# CoCoMEM_RAM.net
KiCad netlist of a schematic drawn in EAGLE
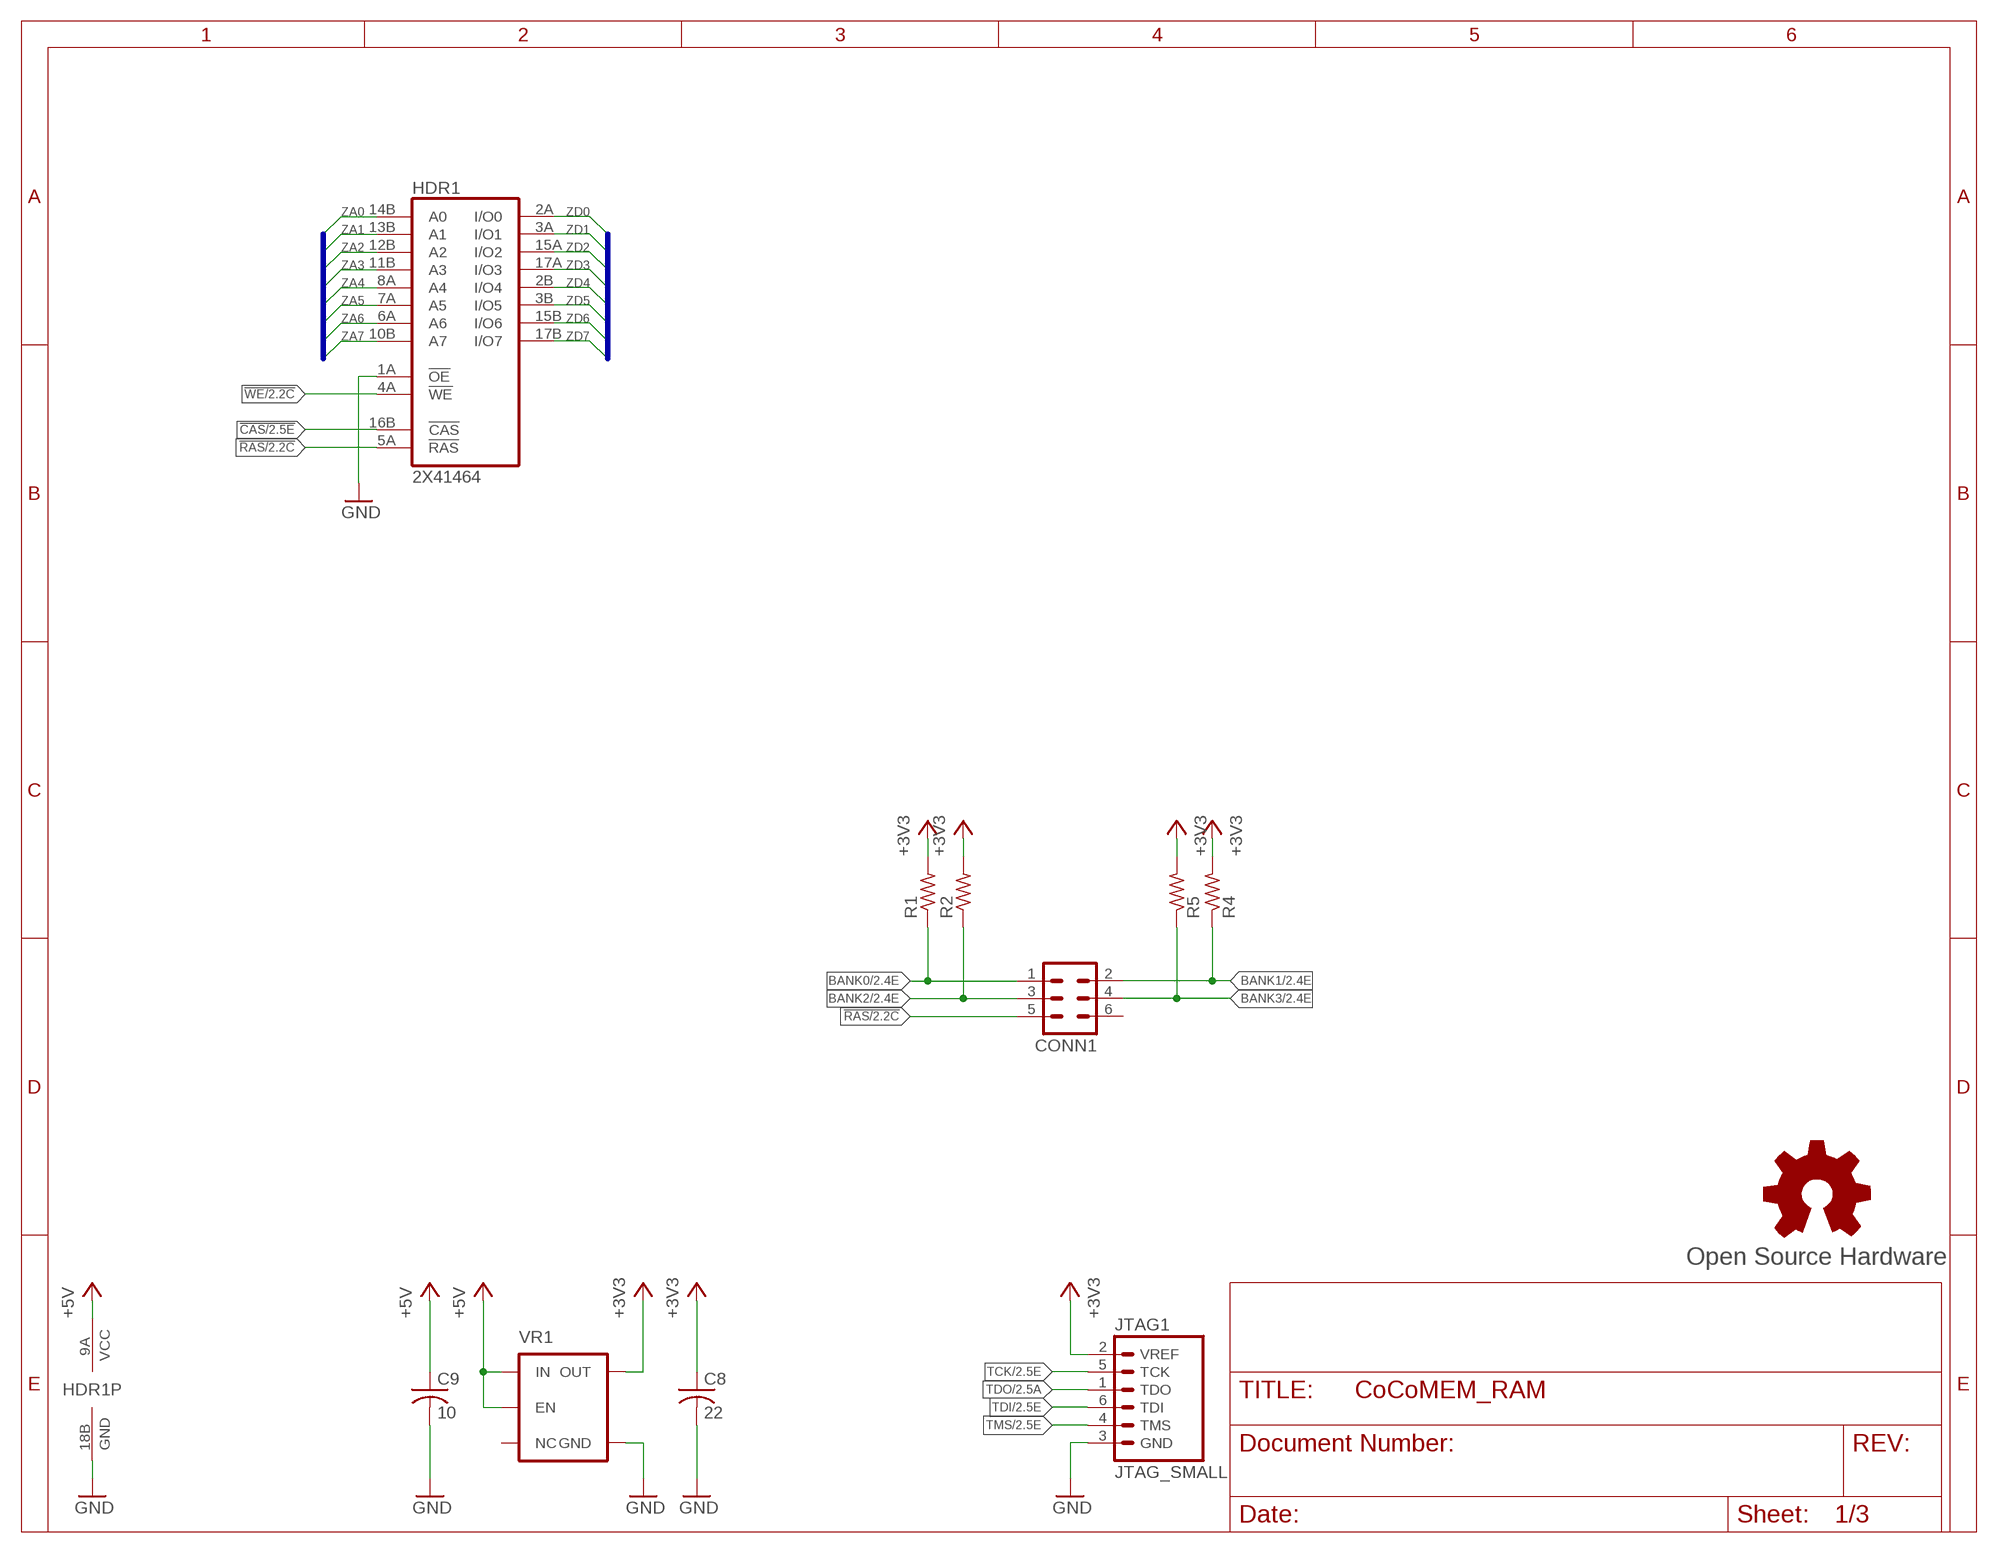
[diagram p0: schematic, sheet 1]
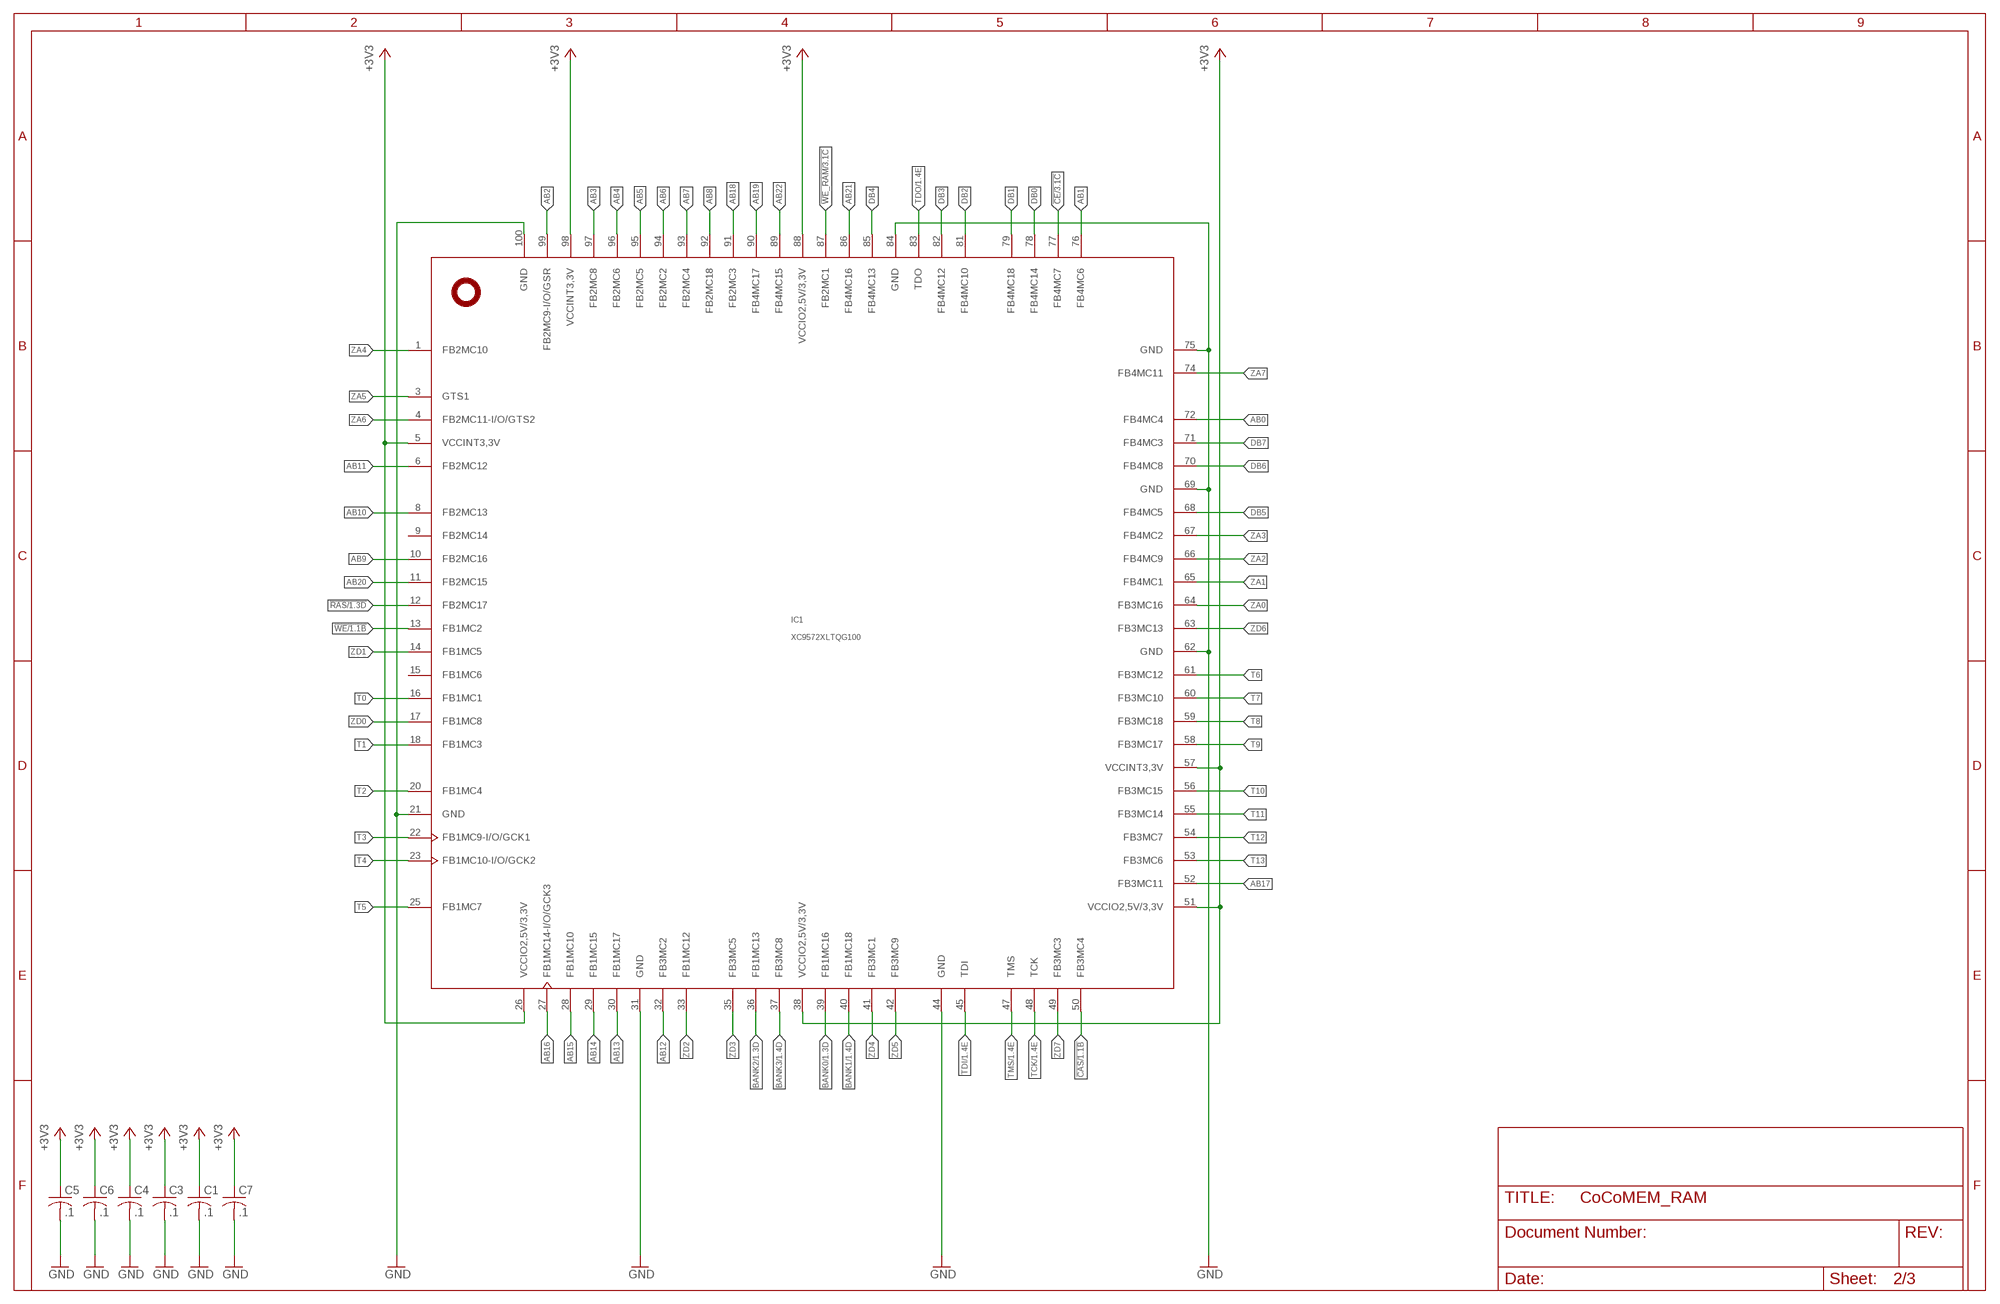
[diagram p1: schematic, sheet 2]
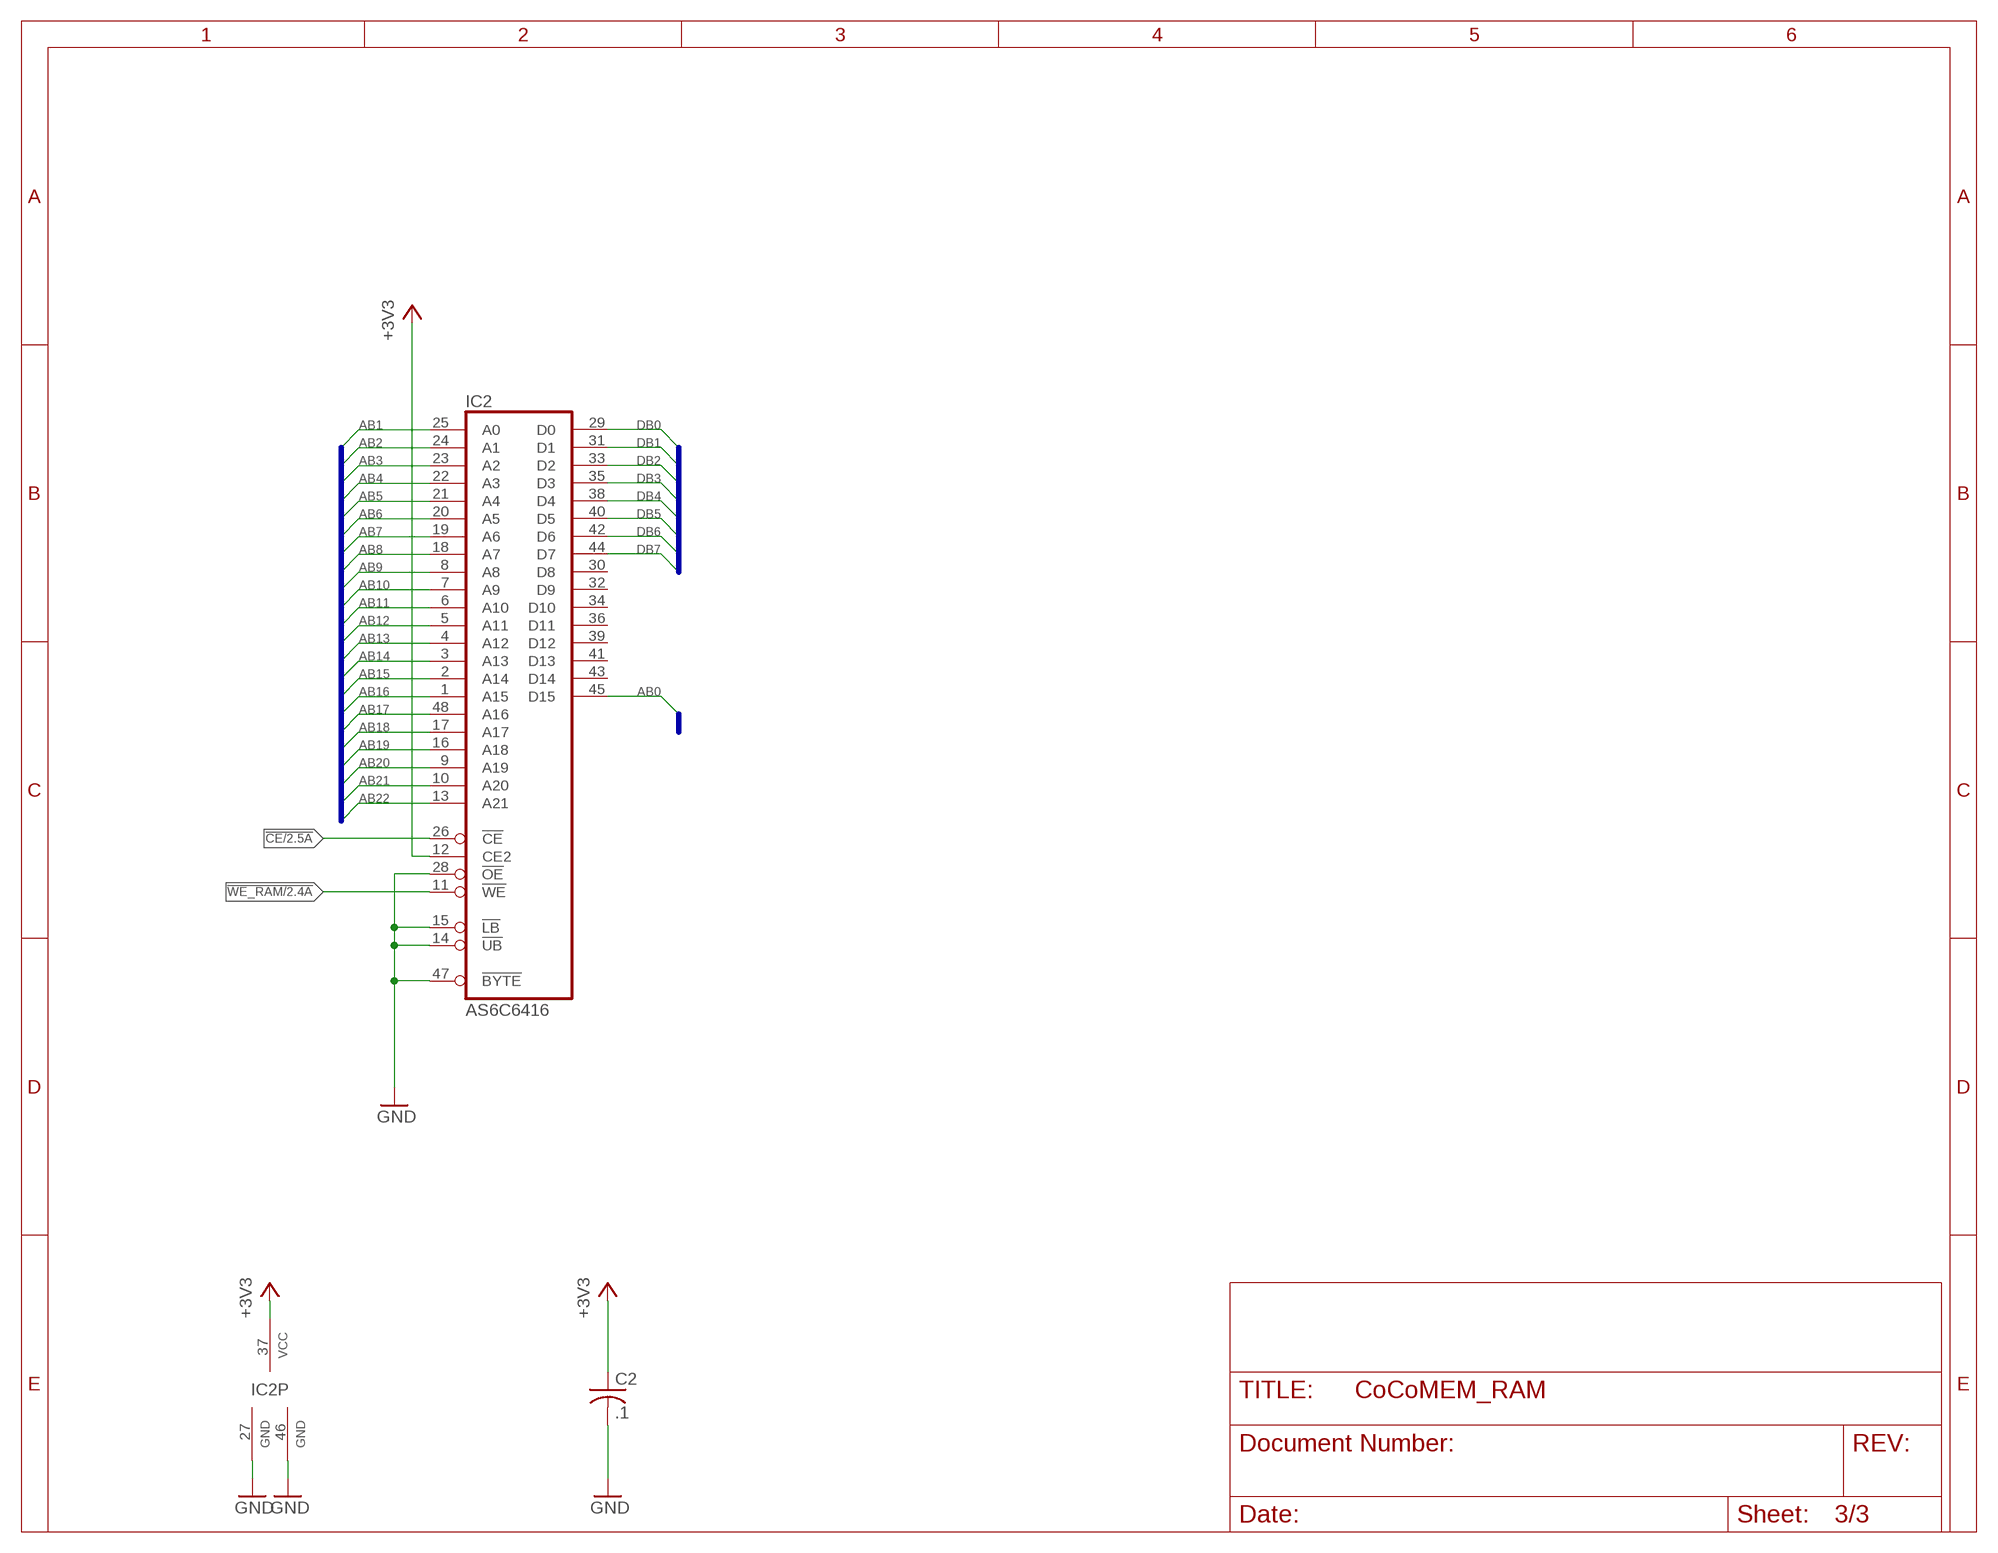
[diagram p2: schematic, sheet 3]

(export (version "E")
  (design (tool "Eeschema 10.0.6"))
  (components
    (comp (ref "C2")
      (value ".1")
      (footprint "eagle-import:C0603")
      (libsource (lib "eagle-import") (part "C-USC0603"))
    )
    (comp (ref "IC2")
      (value "AS6C6416")
      (footprint "eagle-import:TSOP48")
      (libsource (lib "eagle-import") (part "AS6C6416"))
    )
    (comp (ref "C1")
      (value ".1")
      (footprint "eagle-import:C0603")
      (libsource (lib "eagle-import") (part "C-USC0603"))
    )
    (comp (ref "C3")
      (value ".1")
      (footprint "eagle-import:C0603")
      (libsource (lib "eagle-import") (part "C-USC0603"))
    )
    (comp (ref "C4")
      (value ".1")
      (footprint "eagle-import:C0603")
      (libsource (lib "eagle-import") (part "C-USC0603"))
    )
    (comp (ref "C5")
      (value ".1")
      (footprint "eagle-import:C0603")
      (libsource (lib "eagle-import") (part "C-USC0603"))
    )
    (comp (ref "C6")
      (value ".1")
      (footprint "eagle-import:C0603")
      (libsource (lib "eagle-import") (part "C-USC0603"))
    )
    (comp (ref "C7")
      (value ".1")
      (footprint "eagle-import:C0603")
      (libsource (lib "eagle-import") (part "C-USC0603"))
    )
    (comp (ref "IC1")
      (value "XC9572XLTQG100")
      (footprint "eagle-import:TQFP100")
      (libsource (lib "eagle-import") (part "XC9572XLTQG100"))
    )
    (comp (ref "C8")
      (value "22")
      (footprint "eagle-import:C0805")
      (libsource (lib "eagle-import") (part "resistor_C-USC0805"))
    )
    (comp (ref "C9")
      (value "10")
      (footprint "eagle-import:C0805")
      (libsource (lib "eagle-import") (part "resistor_C-USC0805"))
    )
    (comp (ref "CONN1")
      (value "MA03-2")
      (footprint "eagle-import:MA03-2")
      (libsource (lib "eagle-import") (part "MA03-2"))
    )
    (comp (ref "GOLD_ORB_SM1")
      (value "Open Source Hardware")
      (footprint "eagle-import:OSHW_5MM")
      (libsource (lib "eagle-import") (part "OSHWLOGOLOGO5MM"))
    )
    (comp (ref "HDR1")
      (value "2X41464")
      (footprint "eagle-import:2XDIL18_REV")
      (libsource (lib "eagle-import") (part "2X41464"))
    )
    (comp (ref "JTAG1")
      (value "JTAG_SMALL")
      (footprint "eagle-import:JTAG-6")
      (libsource (lib "eagle-import") (part "JTAG_SMALL"))
    )
    (comp (ref "R1")
      (value "R-US_R0402")
      (footprint "eagle-import:R0402")
      (libsource (lib "eagle-import") (part "R-US_R0402"))
    )
    (comp (ref "R2")
      (value "R-US_R0402")
      (footprint "eagle-import:R0402")
      (libsource (lib "eagle-import") (part "R-US_R0402"))
    )
    (comp (ref "R4")
      (value "R-US_R0402")
      (footprint "eagle-import:R0402")
      (libsource (lib "eagle-import") (part "R-US_R0402"))
    )
    (comp (ref "R5")
      (value "R-US_R0402")
      (footprint "eagle-import:R0402")
      (libsource (lib "eagle-import") (part "R-US_R0402"))
    )
    (comp (ref "VR1")
      (value "V_REG_TPS76433SOT23-5")
      (footprint "eagle-import:SOT23-5")
      (libsource (lib "eagle-import") (part "V_REG_TPS76433SOT23-5"))
    )
  )
  (nets
    (net (code "1") (name "+3V3") (class "Default")
      (node (ref "C1") (pin "1") (pinfunction "1_1") (pintype "passive"))
      (node (ref "C2") (pin "1") (pinfunction "1_1") (pintype "passive"))
      (node (ref "C3") (pin "1") (pinfunction "1_1") (pintype "passive"))
      (node (ref "C4") (pin "1") (pinfunction "1_1") (pintype "passive"))
      (node (ref "C5") (pin "1") (pinfunction "1_1") (pintype "passive"))
      (node (ref "C6") (pin "1") (pinfunction "1_1") (pintype "passive"))
      (node (ref "C7") (pin "1") (pinfunction "1_1") (pintype "passive"))
      (node (ref "C8") (pin "1") (pinfunction "1_1") (pintype "passive"))
      (node (ref "IC1") (pin "26") (pinfunction "VCCIO2,5V/3,3V_26") (pintype "power_in"))
      (node (ref "IC1") (pin "38") (pinfunction "VCCIO2,5V/3,3V_38") (pintype "power_in"))
      (node (ref "IC1") (pin "5") (pinfunction "VCCINT3,3V_5") (pintype "power_in"))
      (node (ref "IC1") (pin "51") (pinfunction "VCCIO2,5V/3,3V_51") (pintype "power_in"))
      (node (ref "IC1") (pin "57") (pinfunction "VCCINT3,3V_57") (pintype "power_in"))
      (node (ref "IC1") (pin "88") (pinfunction "VCCIO2,5V/3,3V_88") (pintype "power_in"))
      (node (ref "IC1") (pin "98") (pinfunction "VCCINT3,3V_98") (pintype "power_in"))
      (node (ref "IC2") (pin "12") (pinfunction "CE2_12") (pintype "input"))
      (node (ref "IC2") (pin "37") (pinfunction "VCC_37") (pintype "power_in"))
      (node (ref "JTAG1") (pin "2") (pinfunction "VREF_2") (pintype "power_in"))
      (node (ref "R1") (pin "2") (pinfunction "2_2") (pintype "passive"))
      (node (ref "R2") (pin "2") (pinfunction "2_2") (pintype "passive"))
      (node (ref "R4") (pin "2") (pinfunction "2_2") (pintype "passive"))
      (node (ref "R5") (pin "2") (pinfunction "2_2") (pintype "passive"))
      (node (ref "VR1") (pin "5") (pinfunction "OUT_5") (pintype "passive"))
    )
    (net (code "2") (name "+5V") (class "Default")
      (node (ref "C9") (pin "1") (pinfunction "1_1") (pintype "passive"))
      (node (ref "HDR1") (pin "9A") (pinfunction "VCC_9A") (pintype "power_in"))
      (node (ref "VR1") (pin "1") (pinfunction "IN_1") (pintype "input"))
      (node (ref "VR1") (pin "3") (pinfunction "EN_3") (pintype "input"))
    )
    (net (code "3") (name "AB0") (class "Default")
      (node (ref "IC1") (pin "72") (pinfunction "FB4MC4_72") (pintype "bidirectional"))
      (node (ref "IC2") (pin "45") (pinfunction "D15_45") (pintype "bidirectional"))
    )
    (net (code "4") (name "AB1") (class "Default")
      (node (ref "IC1") (pin "76") (pinfunction "FB4MC6_76") (pintype "bidirectional"))
      (node (ref "IC2") (pin "25") (pinfunction "A0_25") (pintype "input"))
    )
    (net (code "5") (name "AB2") (class "Default")
      (node (ref "IC1") (pin "99") (pinfunction "FB2MC9-I/O/GSR_99") (pintype "bidirectional"))
      (node (ref "IC2") (pin "24") (pinfunction "A1_24") (pintype "input"))
    )
    (net (code "6") (name "AB3") (class "Default")
      (node (ref "IC1") (pin "97") (pinfunction "FB2MC8_97") (pintype "bidirectional"))
      (node (ref "IC2") (pin "23") (pinfunction "A2_23") (pintype "input"))
    )
    (net (code "7") (name "AB4") (class "Default")
      (node (ref "IC1") (pin "96") (pinfunction "FB2MC6_96") (pintype "bidirectional"))
      (node (ref "IC2") (pin "22") (pinfunction "A3_22") (pintype "input"))
    )
    (net (code "8") (name "AB5") (class "Default")
      (node (ref "IC1") (pin "95") (pinfunction "FB2MC5_95") (pintype "bidirectional"))
      (node (ref "IC2") (pin "21") (pinfunction "A4_21") (pintype "input"))
    )
    (net (code "9") (name "AB6") (class "Default")
      (node (ref "IC1") (pin "94") (pinfunction "FB2MC2_94") (pintype "bidirectional"))
      (node (ref "IC2") (pin "20") (pinfunction "A5_20") (pintype "input"))
    )
    (net (code "10") (name "AB7") (class "Default")
      (node (ref "IC1") (pin "93") (pinfunction "FB2MC4_93") (pintype "bidirectional"))
      (node (ref "IC2") (pin "19") (pinfunction "A6_19") (pintype "input"))
    )
    (net (code "11") (name "AB8") (class "Default")
      (node (ref "IC1") (pin "92") (pinfunction "FB2MC18_92") (pintype "bidirectional"))
      (node (ref "IC2") (pin "18") (pinfunction "A7_18") (pintype "input"))
    )
    (net (code "12") (name "AB9") (class "Default")
      (node (ref "IC1") (pin "10") (pinfunction "FB2MC16_10") (pintype "bidirectional"))
      (node (ref "IC2") (pin "8") (pinfunction "A8_8") (pintype "input"))
    )
    (net (code "13") (name "AB10") (class "Default")
      (node (ref "IC1") (pin "8") (pinfunction "FB2MC13_8") (pintype "bidirectional"))
      (node (ref "IC2") (pin "7") (pinfunction "A9_7") (pintype "input"))
    )
    (net (code "14") (name "AB11") (class "Default")
      (node (ref "IC1") (pin "6") (pinfunction "FB2MC12_6") (pintype "bidirectional"))
      (node (ref "IC2") (pin "6") (pinfunction "A10_6") (pintype "input"))
    )
    (net (code "15") (name "AB12") (class "Default")
      (node (ref "IC1") (pin "32") (pinfunction "FB3MC2_32") (pintype "bidirectional"))
      (node (ref "IC2") (pin "5") (pinfunction "A11_5") (pintype "input"))
    )
    (net (code "16") (name "AB13") (class "Default")
      (node (ref "IC1") (pin "30") (pinfunction "FB1MC17_30") (pintype "bidirectional"))
      (node (ref "IC2") (pin "4") (pinfunction "A12_4") (pintype "input"))
    )
    (net (code "17") (name "AB14") (class "Default")
      (node (ref "IC1") (pin "29") (pinfunction "FB1MC15_29") (pintype "bidirectional"))
      (node (ref "IC2") (pin "3") (pinfunction "A13_3") (pintype "input"))
    )
    (net (code "18") (name "AB15") (class "Default")
      (node (ref "IC1") (pin "28") (pinfunction "FB1MC10_28") (pintype "bidirectional"))
      (node (ref "IC2") (pin "2") (pinfunction "A14_2") (pintype "input"))
    )
    (net (code "19") (name "AB16") (class "Default")
      (node (ref "IC1") (pin "27") (pinfunction "FB1MC14-I/O/GCK3_27") (pintype "bidirectional"))
      (node (ref "IC2") (pin "1") (pinfunction "A15_1") (pintype "input"))
    )
    (net (code "20") (name "AB17") (class "Default")
      (node (ref "IC1") (pin "52") (pinfunction "FB3MC11_52") (pintype "bidirectional"))
      (node (ref "IC2") (pin "48") (pinfunction "A16_48") (pintype "input"))
    )
    (net (code "21") (name "AB18") (class "Default")
      (node (ref "IC1") (pin "91") (pinfunction "FB2MC3_91") (pintype "bidirectional"))
      (node (ref "IC2") (pin "17") (pinfunction "A17_17") (pintype "input"))
    )
    (net (code "22") (name "AB19") (class "Default")
      (node (ref "IC1") (pin "90") (pinfunction "FB4MC17_90") (pintype "bidirectional"))
      (node (ref "IC2") (pin "16") (pinfunction "A18_16") (pintype "input"))
    )
    (net (code "23") (name "AB20") (class "Default")
      (node (ref "IC1") (pin "11") (pinfunction "FB2MC15_11") (pintype "bidirectional"))
      (node (ref "IC2") (pin "9") (pinfunction "A19_9") (pintype "input"))
    )
    (net (code "24") (name "AB21") (class "Default")
      (node (ref "IC1") (pin "86") (pinfunction "FB4MC16_86") (pintype "bidirectional"))
      (node (ref "IC2") (pin "10") (pinfunction "A20_10") (pintype "input"))
    )
    (net (code "25") (name "AB22") (class "Default")
      (node (ref "IC1") (pin "89") (pinfunction "FB4MC15_89") (pintype "bidirectional"))
      (node (ref "IC2") (pin "13") (pinfunction "A21_13") (pintype "input"))
    )
    (net (code "26") (name "BANK0") (class "Default")
      (node (ref "CONN1") (pin "1") (pinfunction "1_1") (pintype "passive"))
      (node (ref "IC1") (pin "39") (pinfunction "FB1MC16_39") (pintype "bidirectional"))
      (node (ref "R1") (pin "1") (pinfunction "1_1") (pintype "passive"))
    )
    (net (code "27") (name "BANK1") (class "Default")
      (node (ref "CONN1") (pin "2") (pinfunction "2_2") (pintype "passive"))
      (node (ref "IC1") (pin "40") (pinfunction "FB1MC18_40") (pintype "bidirectional"))
      (node (ref "R4") (pin "1") (pinfunction "1_1") (pintype "passive"))
    )
    (net (code "28") (name "BANK2") (class "Default")
      (node (ref "CONN1") (pin "3") (pinfunction "3_3") (pintype "passive"))
      (node (ref "IC1") (pin "36") (pinfunction "FB1MC13_36") (pintype "bidirectional"))
      (node (ref "R2") (pin "1") (pinfunction "1_1") (pintype "passive"))
    )
    (net (code "29") (name "BANK3") (class "Default")
      (node (ref "CONN1") (pin "4") (pinfunction "4_4") (pintype "passive"))
      (node (ref "IC1") (pin "37") (pinfunction "FB3MC8_37") (pintype "bidirectional"))
      (node (ref "R5") (pin "1") (pinfunction "1_1") (pintype "passive"))
    )
    (net (code "30") (name "DB0") (class "Default")
      (node (ref "IC1") (pin "78") (pinfunction "FB4MC14_78") (pintype "bidirectional"))
      (node (ref "IC2") (pin "29") (pinfunction "D0_29") (pintype "bidirectional"))
    )
    (net (code "31") (name "DB1") (class "Default")
      (node (ref "IC1") (pin "79") (pinfunction "FB4MC18_79") (pintype "bidirectional"))
      (node (ref "IC2") (pin "31") (pinfunction "D1_31") (pintype "bidirectional"))
    )
    (net (code "32") (name "DB2") (class "Default")
      (node (ref "IC1") (pin "81") (pinfunction "FB4MC10_81") (pintype "bidirectional"))
      (node (ref "IC2") (pin "33") (pinfunction "D2_33") (pintype "bidirectional"))
    )
    (net (code "33") (name "DB3") (class "Default")
      (node (ref "IC1") (pin "82") (pinfunction "FB4MC12_82") (pintype "bidirectional"))
      (node (ref "IC2") (pin "35") (pinfunction "D3_35") (pintype "bidirectional"))
    )
    (net (code "34") (name "DB4") (class "Default")
      (node (ref "IC1") (pin "85") (pinfunction "FB4MC13_85") (pintype "bidirectional"))
      (node (ref "IC2") (pin "38") (pinfunction "D4_38") (pintype "bidirectional"))
    )
    (net (code "35") (name "DB5") (class "Default")
      (node (ref "IC1") (pin "68") (pinfunction "FB4MC5_68") (pintype "bidirectional"))
      (node (ref "IC2") (pin "40") (pinfunction "D5_40") (pintype "bidirectional"))
    )
    (net (code "36") (name "DB6") (class "Default")
      (node (ref "IC1") (pin "70") (pinfunction "FB4MC8_70") (pintype "bidirectional"))
      (node (ref "IC2") (pin "42") (pinfunction "D6_42") (pintype "bidirectional"))
    )
    (net (code "37") (name "DB7") (class "Default")
      (node (ref "IC1") (pin "71") (pinfunction "FB4MC3_71") (pintype "bidirectional"))
      (node (ref "IC2") (pin "44") (pinfunction "D7_44") (pintype "bidirectional"))
    )
    (net (code "38") (name "GND") (class "Default")
      (node (ref "C1") (pin "2") (pinfunction "2_2") (pintype "passive"))
      (node (ref "C2") (pin "2") (pinfunction "2_2") (pintype "passive"))
      (node (ref "C3") (pin "2") (pinfunction "2_2") (pintype "passive"))
      (node (ref "C4") (pin "2") (pinfunction "2_2") (pintype "passive"))
      (node (ref "C5") (pin "2") (pinfunction "2_2") (pintype "passive"))
      (node (ref "C6") (pin "2") (pinfunction "2_2") (pintype "passive"))
      (node (ref "C7") (pin "2") (pinfunction "2_2") (pintype "passive"))
      (node (ref "C8") (pin "2") (pinfunction "2_2") (pintype "passive"))
      (node (ref "C9") (pin "2") (pinfunction "2_2") (pintype "passive"))
      (node (ref "HDR1") (pin "18B") (pinfunction "GND_18B") (pintype "power_in"))
      (node (ref "HDR1") (pin "1A") (pinfunction "~{OE}_1A") (pintype "input"))
      (node (ref "IC1") (pin "100") (pinfunction "GND_100") (pintype "power_in"))
      (node (ref "IC1") (pin "21") (pinfunction "GND_21") (pintype "power_in"))
      (node (ref "IC1") (pin "31") (pinfunction "GND_31") (pintype "power_in"))
      (node (ref "IC1") (pin "44") (pinfunction "GND_44") (pintype "power_in"))
      (node (ref "IC1") (pin "62") (pinfunction "GND_62") (pintype "power_in"))
      (node (ref "IC1") (pin "69") (pinfunction "GND_69") (pintype "power_in"))
      (node (ref "IC1") (pin "75") (pinfunction "GND_75") (pintype "power_in"))
      (node (ref "IC1") (pin "84") (pinfunction "GND_84") (pintype "power_in"))
      (node (ref "IC2") (pin "14") (pinfunction "~{UB}_14") (pintype "input"))
      (node (ref "IC2") (pin "15") (pinfunction "~{LB}_15") (pintype "input"))
      (node (ref "IC2") (pin "27") (pinfunction "GND_27") (pintype "power_in"))
      (node (ref "IC2") (pin "28") (pinfunction "~{OE}_28") (pintype "input"))
      (node (ref "IC2") (pin "46") (pinfunction "GND_46") (pintype "power_in"))
      (node (ref "IC2") (pin "47") (pinfunction "~{BYTE}_47") (pintype "input"))
      (node (ref "JTAG1") (pin "3") (pinfunction "GND_3") (pintype "power_in"))
      (node (ref "VR1") (pin "2") (pinfunction "GND_2") (pintype "input"))
    )
    (net (code "39") (name "T0") (class "Default")
      (node (ref "IC1") (pin "16") (pinfunction "FB1MC1_16") (pintype "bidirectional"))
    )
    (net (code "40") (name "T1") (class "Default")
      (node (ref "IC1") (pin "18") (pinfunction "FB1MC3_18") (pintype "bidirectional"))
    )
    (net (code "41") (name "T2") (class "Default")
      (node (ref "IC1") (pin "20") (pinfunction "FB1MC4_20") (pintype "bidirectional"))
    )
    (net (code "42") (name "T3") (class "Default")
      (node (ref "IC1") (pin "22") (pinfunction "FB1MC9-I/O/GCK1_22") (pintype "bidirectional"))
    )
    (net (code "43") (name "T4") (class "Default")
      (node (ref "IC1") (pin "23") (pinfunction "FB1MC10-I/O/GCK2_23") (pintype "bidirectional"))
    )
    (net (code "44") (name "T5") (class "Default")
      (node (ref "IC1") (pin "25") (pinfunction "FB1MC7_25") (pintype "bidirectional"))
    )
    (net (code "45") (name "T6") (class "Default")
      (node (ref "IC1") (pin "61") (pinfunction "FB3MC12_61") (pintype "bidirectional"))
    )
    (net (code "46") (name "T7") (class "Default")
      (node (ref "IC1") (pin "60") (pinfunction "FB3MC10_60") (pintype "bidirectional"))
    )
    (net (code "47") (name "T8") (class "Default")
      (node (ref "IC1") (pin "59") (pinfunction "FB3MC18_59") (pintype "bidirectional"))
    )
    (net (code "48") (name "T9") (class "Default")
      (node (ref "IC1") (pin "58") (pinfunction "FB3MC17_58") (pintype "bidirectional"))
    )
    (net (code "49") (name "T10") (class "Default")
      (node (ref "IC1") (pin "56") (pinfunction "FB3MC15_56") (pintype "bidirectional"))
    )
    (net (code "50") (name "T11") (class "Default")
      (node (ref "IC1") (pin "55") (pinfunction "FB3MC14_55") (pintype "bidirectional"))
    )
    (net (code "51") (name "T12") (class "Default")
      (node (ref "IC1") (pin "54") (pinfunction "FB3MC7_54") (pintype "bidirectional"))
    )
    (net (code "52") (name "T13") (class "Default")
      (node (ref "IC1") (pin "53") (pinfunction "FB3MC6_53") (pintype "bidirectional"))
    )
    (net (code "53") (name "TCK") (class "Default")
      (node (ref "IC1") (pin "48") (pinfunction "TCK_48") (pintype "bidirectional"))
      (node (ref "JTAG1") (pin "5") (pinfunction "TCK_5") (pintype "output"))
    )
    (net (code "54") (name "TDI") (class "Default")
      (node (ref "IC1") (pin "45") (pinfunction "TDI_45") (pintype "bidirectional"))
      (node (ref "JTAG1") (pin "6") (pinfunction "TDI_6") (pintype "input"))
    )
    (net (code "55") (name "TDO") (class "Default")
      (node (ref "IC1") (pin "83") (pinfunction "TDO_83") (pintype "bidirectional"))
      (node (ref "JTAG1") (pin "1") (pinfunction "TDO_1") (pintype "output"))
    )
    (net (code "56") (name "TMS") (class "Default")
      (node (ref "IC1") (pin "47") (pinfunction "TMS_47") (pintype "bidirectional"))
      (node (ref "JTAG1") (pin "4") (pinfunction "TMS_4") (pintype "output"))
    )
    (net (code "57") (name "ZA0") (class "Default")
      (node (ref "HDR1") (pin "14B") (pinfunction "A0_14B") (pintype "input"))
      (node (ref "IC1") (pin "64") (pinfunction "FB3MC16_64") (pintype "bidirectional"))
    )
    (net (code "58") (name "ZA1") (class "Default")
      (node (ref "HDR1") (pin "13B") (pinfunction "A1_13B") (pintype "input"))
      (node (ref "IC1") (pin "65") (pinfunction "FB4MC1_65") (pintype "bidirectional"))
    )
    (net (code "59") (name "ZA2") (class "Default")
      (node (ref "HDR1") (pin "12B") (pinfunction "A2_12B") (pintype "input"))
      (node (ref "IC1") (pin "66") (pinfunction "FB4MC9_66") (pintype "bidirectional"))
    )
    (net (code "60") (name "ZA3") (class "Default")
      (node (ref "HDR1") (pin "11B") (pinfunction "A3_11B") (pintype "input"))
      (node (ref "IC1") (pin "67") (pinfunction "FB4MC2_67") (pintype "bidirectional"))
    )
    (net (code "61") (name "ZA4") (class "Default")
      (node (ref "HDR1") (pin "8A") (pinfunction "A4_8A") (pintype "input"))
      (node (ref "IC1") (pin "1") (pinfunction "FB2MC10_1") (pintype "bidirectional"))
    )
    (net (code "62") (name "ZA5") (class "Default")
      (node (ref "HDR1") (pin "7A") (pinfunction "A5_7A") (pintype "input"))
      (node (ref "IC1") (pin "3") (pinfunction "GTS1_3") (pintype "bidirectional"))
    )
    (net (code "63") (name "ZA6") (class "Default")
      (node (ref "HDR1") (pin "6A") (pinfunction "A6_6A") (pintype "input"))
      (node (ref "IC1") (pin "4") (pinfunction "FB2MC11-I/O/GTS2_4") (pintype "bidirectional"))
    )
    (net (code "64") (name "ZA7") (class "Default")
      (node (ref "HDR1") (pin "10B") (pinfunction "A7_10B") (pintype "input"))
      (node (ref "IC1") (pin "74") (pinfunction "FB4MC11_74") (pintype "bidirectional"))
    )
    (net (code "65") (name "ZD0") (class "Default")
      (node (ref "HDR1") (pin "2A") (pinfunction "I/O0_2A") (pintype "bidirectional"))
      (node (ref "IC1") (pin "17") (pinfunction "FB1MC8_17") (pintype "bidirectional"))
    )
    (net (code "66") (name "ZD1") (class "Default")
      (node (ref "HDR1") (pin "3A") (pinfunction "I/O1_3A") (pintype "bidirectional"))
      (node (ref "IC1") (pin "14") (pinfunction "FB1MC5_14") (pintype "bidirectional"))
    )
    (net (code "67") (name "ZD2") (class "Default")
      (node (ref "HDR1") (pin "15A") (pinfunction "I/O2_15A") (pintype "bidirectional"))
      (node (ref "IC1") (pin "33") (pinfunction "FB1MC12_33") (pintype "bidirectional"))
    )
    (net (code "68") (name "ZD3") (class "Default")
      (node (ref "HDR1") (pin "17A") (pinfunction "I/O3_17A") (pintype "bidirectional"))
      (node (ref "IC1") (pin "35") (pinfunction "FB3MC5_35") (pintype "bidirectional"))
    )
    (net (code "69") (name "ZD4") (class "Default")
      (node (ref "HDR1") (pin "2B") (pinfunction "I/O4_2B") (pintype "bidirectional"))
      (node (ref "IC1") (pin "41") (pinfunction "FB3MC1_41") (pintype "bidirectional"))
    )
    (net (code "70") (name "ZD5") (class "Default")
      (node (ref "HDR1") (pin "3B") (pinfunction "I/O5_3B") (pintype "bidirectional"))
      (node (ref "IC1") (pin "42") (pinfunction "FB3MC9_42") (pintype "bidirectional"))
    )
    (net (code "71") (name "ZD6") (class "Default")
      (node (ref "HDR1") (pin "15B") (pinfunction "I/O6_15B") (pintype "bidirectional"))
      (node (ref "IC1") (pin "63") (pinfunction "FB3MC13_63") (pintype "bidirectional"))
    )
    (net (code "72") (name "ZD7") (class "Default")
      (node (ref "HDR1") (pin "17B") (pinfunction "I/O7_17B") (pintype "bidirectional"))
      (node (ref "IC1") (pin "49") (pinfunction "FB3MC3_49") (pintype "bidirectional"))
    )
    (net (code "73") (name "unconnected-(CONN1-Pad6)") (class "Default")
      (node (ref "CONN1") (pin "6") (pinfunction "6_6") (pintype "passive"))
    )
    (net (code "74") (name "unconnected-(IC1-FB1MC6-Pad15)") (class "Default")
      (node (ref "IC1") (pin "15") (pinfunction "FB1MC6_15") (pintype "bidirectional"))
    )
    (net (code "75") (name "unconnected-(IC1-FB2MC14-Pad9)") (class "Default")
      (node (ref "IC1") (pin "9") (pinfunction "FB2MC14_9") (pintype "bidirectional"))
    )
    (net (code "76") (name "unconnected-(IC2A-D8-Pad30)") (class "Default")
      (node (ref "IC2") (pin "30") (pinfunction "D8_30") (pintype "bidirectional"))
    )
    (net (code "77") (name "unconnected-(IC2A-D9-Pad32)") (class "Default")
      (node (ref "IC2") (pin "32") (pinfunction "D9_32") (pintype "bidirectional"))
    )
    (net (code "78") (name "unconnected-(IC2A-D10-Pad34)") (class "Default")
      (node (ref "IC2") (pin "34") (pinfunction "D10_34") (pintype "bidirectional"))
    )
    (net (code "79") (name "unconnected-(IC2A-D11-Pad36)") (class "Default")
      (node (ref "IC2") (pin "36") (pinfunction "D11_36") (pintype "bidirectional"))
    )
    (net (code "80") (name "unconnected-(IC2A-D12-Pad39)") (class "Default")
      (node (ref "IC2") (pin "39") (pinfunction "D12_39") (pintype "bidirectional"))
    )
    (net (code "81") (name "unconnected-(IC2A-D13-Pad41)") (class "Default")
      (node (ref "IC2") (pin "41") (pinfunction "D13_41") (pintype "bidirectional"))
    )
    (net (code "82") (name "unconnected-(IC2A-D14-Pad43)") (class "Default")
      (node (ref "IC2") (pin "43") (pinfunction "D14_43") (pintype "bidirectional"))
    )
    (net (code "83") (name "unconnected-(VR1-NC-Pad4)") (class "Default")
      (node (ref "VR1") (pin "4") (pinfunction "NC_4") (pintype "input"))
    )
    (net (code "84") (name "~{CAS}") (class "Default")
      (node (ref "HDR1") (pin "16B") (pinfunction "~{CAS}_16B") (pintype "input"))
      (node (ref "IC1") (pin "50") (pinfunction "FB3MC4_50") (pintype "bidirectional"))
    )
    (net (code "85") (name "~{CE}") (class "Default")
      (node (ref "IC1") (pin "77") (pinfunction "FB4MC7_77") (pintype "bidirectional"))
      (node (ref "IC2") (pin "26") (pinfunction "~{CE}_26") (pintype "input"))
    )
    (net (code "86") (name "~{RAS}") (class "Default")
      (node (ref "CONN1") (pin "5") (pinfunction "5_5") (pintype "passive"))
      (node (ref "HDR1") (pin "5A") (pinfunction "~{RAS}_5A") (pintype "input"))
      (node (ref "IC1") (pin "12") (pinfunction "FB2MC17_12") (pintype "bidirectional"))
    )
    (net (code "87") (name "~{WE_RAM}") (class "Default")
      (node (ref "IC1") (pin "87") (pinfunction "FB2MC1_87") (pintype "bidirectional"))
      (node (ref "IC2") (pin "11") (pinfunction "~{WE}_11") (pintype "input"))
    )
    (net (code "88") (name "~{WE}") (class "Default")
      (node (ref "HDR1") (pin "4A") (pinfunction "~{WE}_4A") (pintype "input"))
      (node (ref "IC1") (pin "13") (pinfunction "FB1MC2_13") (pintype "bidirectional"))
    )
  )
)
